# PWM-Generator.net
KiCad netlist of a schematic drawn in Altium Designer
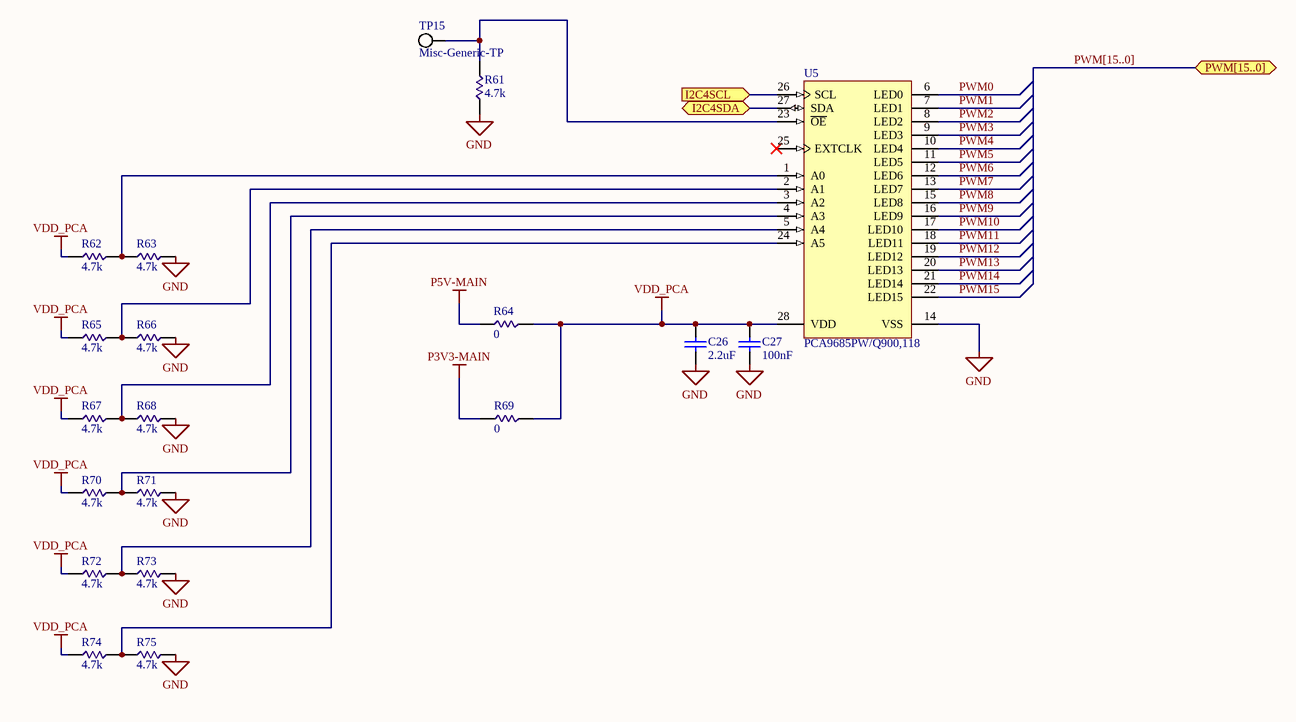
[diagram p0: PWM-Generator.SchDoc]

(export (version "E")
  (design (tool "Eeschema 10.0.6"))
  (components
    (comp (ref "C26")
      (value "2.2uF")
      (footprint "FOOTPRINT-0805-GEN")
      (description "Capacitor")
      (fields (field (name "Comment") "C0805C225K8RACTU") (field (name "PUBLISHER") "Altium Limited"))
      (libsource (lib "HR-Master-Integrated") (part "Capacitor-Generic-0805"))
    )
    (comp (ref "C27")
      (value "100nF")
      (footprint "FOOTPRINT-0805-GEN")
      (description "Capacitor")
      (fields (field (name "Comment") "C0805C104K8RACTU") (field (name "PUBLISHER") "Altium Limited"))
      (libsource (lib "HR-Master-Integrated") (part "Capacitor-Generic-0805"))
    )
    (comp (ref "R61")
      (value "4.7k")
      (footprint "FOOTPRINT-0805-GEN")
      (description "1/8 Watt Surface Mount Resistor")
      (fields (field (name "Comment") "SMC"))
      (libsource (lib "HR-Master-Integrated") (part "Resistor-Generic-0805-2012"))
    )
    (comp (ref "R62")
      (value "4.7k")
      (footprint "FOOTPRINT-0805-GEN")
      (description "1/8 Watt Surface Mount Resistor")
      (fields (field (name "Comment") "SMC"))
      (libsource (lib "HR-Master-Integrated") (part "Resistor-Generic-0805-2012"))
    )
    (comp (ref "R63")
      (value "4.7k")
      (footprint "FOOTPRINT-0805-GEN")
      (description "1/8 Watt Surface Mount Resistor")
      (fields (field (name "Comment") "SMC"))
      (libsource (lib "HR-Master-Integrated") (part "Resistor-Generic-0805-2012"))
    )
    (comp (ref "R64")
      (value "0")
      (footprint "FOOTPRINT-0805-GEN")
      (description "1/8 Watt Surface Mount Resistor")
      (fields (field (name "Comment") "SMC"))
      (libsource (lib "HR-Master-Integrated") (part "Resistor-Generic-0805-2012"))
    )
    (comp (ref "R65")
      (value "4.7k")
      (footprint "FOOTPRINT-0805-GEN")
      (description "1/8 Watt Surface Mount Resistor")
      (fields (field (name "Comment") "SMC"))
      (libsource (lib "HR-Master-Integrated") (part "Resistor-Generic-0805-2012"))
    )
    (comp (ref "R66")
      (value "4.7k")
      (footprint "FOOTPRINT-0805-GEN")
      (description "1/8 Watt Surface Mount Resistor")
      (fields (field (name "Comment") "SMC"))
      (libsource (lib "HR-Master-Integrated") (part "Resistor-Generic-0805-2012"))
    )
    (comp (ref "R67")
      (value "4.7k")
      (footprint "FOOTPRINT-0805-GEN")
      (description "1/8 Watt Surface Mount Resistor")
      (fields (field (name "Comment") "SMC"))
      (libsource (lib "HR-Master-Integrated") (part "Resistor-Generic-0805-2012"))
    )
    (comp (ref "R68")
      (value "4.7k")
      (footprint "FOOTPRINT-0805-GEN")
      (description "1/8 Watt Surface Mount Resistor")
      (fields (field (name "Comment") "SMC"))
      (libsource (lib "HR-Master-Integrated") (part "Resistor-Generic-0805-2012"))
    )
    (comp (ref "R69")
      (value "0")
      (footprint "FOOTPRINT-0805-GEN")
      (description "1/8 Watt Surface Mount Resistor")
      (fields (field (name "Comment") "SMC"))
      (libsource (lib "HR-Master-Integrated") (part "Resistor-Generic-0805-2012"))
    )
    (comp (ref "R70")
      (value "4.7k")
      (footprint "FOOTPRINT-0805-GEN")
      (description "1/8 Watt Surface Mount Resistor")
      (fields (field (name "Comment") "SMC"))
      (libsource (lib "HR-Master-Integrated") (part "Resistor-Generic-0805-2012"))
    )
    (comp (ref "R71")
      (value "4.7k")
      (footprint "FOOTPRINT-0805-GEN")
      (description "1/8 Watt Surface Mount Resistor")
      (fields (field (name "Comment") "SMC"))
      (libsource (lib "HR-Master-Integrated") (part "Resistor-Generic-0805-2012"))
    )
    (comp (ref "R72")
      (value "4.7k")
      (footprint "FOOTPRINT-0805-GEN")
      (description "1/8 Watt Surface Mount Resistor")
      (fields (field (name "Comment") "SMC"))
      (libsource (lib "HR-Master-Integrated") (part "Resistor-Generic-0805-2012"))
    )
    (comp (ref "R73")
      (value "4.7k")
      (footprint "FOOTPRINT-0805-GEN")
      (description "1/8 Watt Surface Mount Resistor")
      (fields (field (name "Comment") "SMC"))
      (libsource (lib "HR-Master-Integrated") (part "Resistor-Generic-0805-2012"))
    )
    (comp (ref "R74")
      (value "4.7k")
      (footprint "FOOTPRINT-0805-GEN")
      (description "1/8 Watt Surface Mount Resistor")
      (fields (field (name "Comment") "SMC"))
      (libsource (lib "HR-Master-Integrated") (part "Resistor-Generic-0805-2012"))
    )
    (comp (ref "R75")
      (value "4.7k")
      (footprint "FOOTPRINT-0805-GEN")
      (description "1/8 Watt Surface Mount Resistor")
      (fields (field (name "Comment") "SMC"))
      (libsource (lib "HR-Master-Integrated") (part "Resistor-Generic-0805-2012"))
    )
    (comp (ref "TP15")
      (value "Misc-Generic-TP")
      (footprint "FOOTPRINT-GENERIC-TP-VIA-1MM")
      (libsource (lib "Generic") (part "Misc-Generic-TP"))
    )
    (comp (ref "U5")
      (value "PCA9685PW/Q900,118")
      (footprint "FOOTPRINT-NXP-PCA9685")
      (fields (field (name "PARTNUMBER") "PCA9685"))
      (libsource (lib "HR-Master-Integrated") (part "IC-NXP-PCA9685"))
    )
  )
  (nets
    (net (code "1") (name "/I2C4SCL") (class "Default")
      (node (ref "U5") (pin "26") (pinfunction "SCL_26") (pintype "input"))
    )
    (net (code "2") (name "/I2C4SDA") (class "Default")
      (node (ref "U5") (pin "27") (pinfunction "SDA_27") (pintype "bidirectional"))
    )
    (net (code "3") (name "/PWM0") (class "Default")
      (node (ref "U5") (pin "6") (pinfunction "LED0_6") (pintype "tri_state"))
    )
    (net (code "4") (name "/PWM1") (class "Default")
      (node (ref "U5") (pin "7") (pinfunction "LED1_7") (pintype "tri_state"))
    )
    (net (code "5") (name "/PWM2") (class "Default")
      (node (ref "U5") (pin "8") (pinfunction "LED2_8") (pintype "tri_state"))
    )
    (net (code "6") (name "/PWM3") (class "Default")
      (node (ref "U5") (pin "9") (pinfunction "LED3_9") (pintype "tri_state"))
    )
    (net (code "7") (name "/PWM4") (class "Default")
      (node (ref "U5") (pin "10") (pinfunction "LED4_10") (pintype "tri_state"))
    )
    (net (code "8") (name "/PWM5") (class "Default")
      (node (ref "U5") (pin "11") (pinfunction "LED5_11") (pintype "tri_state"))
    )
    (net (code "9") (name "/PWM6") (class "Default")
      (node (ref "U5") (pin "12") (pinfunction "LED6_12") (pintype "tri_state"))
    )
    (net (code "10") (name "/PWM7") (class "Default")
      (node (ref "U5") (pin "13") (pinfunction "LED7_13") (pintype "tri_state"))
    )
    (net (code "11") (name "/PWM8") (class "Default")
      (node (ref "U5") (pin "15") (pinfunction "LED8_15") (pintype "tri_state"))
    )
    (net (code "12") (name "/PWM9") (class "Default")
      (node (ref "U5") (pin "16") (pinfunction "LED9_16") (pintype "tri_state"))
    )
    (net (code "13") (name "/PWM10") (class "Default")
      (node (ref "U5") (pin "17") (pinfunction "LED10_17") (pintype "tri_state"))
    )
    (net (code "14") (name "/PWM11") (class "Default")
      (node (ref "U5") (pin "18") (pinfunction "LED11_18") (pintype "tri_state"))
    )
    (net (code "15") (name "/PWM12") (class "Default")
      (node (ref "U5") (pin "19") (pinfunction "LED12_19") (pintype "tri_state"))
    )
    (net (code "16") (name "/PWM13") (class "Default")
      (node (ref "U5") (pin "20") (pinfunction "LED13_20") (pintype "tri_state"))
    )
    (net (code "17") (name "/PWM14") (class "Default")
      (node (ref "U5") (pin "21") (pinfunction "LED14_21") (pintype "tri_state"))
    )
    (net (code "18") (name "/PWM15") (class "Default")
      (node (ref "U5") (pin "22") (pinfunction "LED15_22") (pintype "tri_state"))
    )
    (net (code "20") (name "GND") (class "Default")
      (node (ref "C26") (pin "2") (pinfunction "2_2") (pintype "passive"))
      (node (ref "C27") (pin "1") (pinfunction "1_1") (pintype "passive"))
      (node (ref "R61") (pin "1") (pinfunction "1_1") (pintype "passive"))
      (node (ref "R63") (pin "2") (pinfunction "2_2") (pintype "passive"))
      (node (ref "R66") (pin "2") (pinfunction "2_2") (pintype "passive"))
      (node (ref "R68") (pin "2") (pinfunction "2_2") (pintype "passive"))
      (node (ref "R71") (pin "2") (pinfunction "2_2") (pintype "passive"))
      (node (ref "R73") (pin "2") (pinfunction "2_2") (pintype "passive"))
      (node (ref "R75") (pin "2") (pinfunction "2_2") (pintype "passive"))
      (node (ref "U5") (pin "14") (pinfunction "VSS_14") (pintype "power_in"))
    )
    (net (code "21") (name "Net-(TP15-TP)") (class "Default")
      (node (ref "R61") (pin "2") (pinfunction "2_2") (pintype "passive"))
      (node (ref "TP15") (pin "1") (pinfunction "TP_1") (pintype "passive"))
      (node (ref "U5") (pin "23") (pinfunction "~{OE}_23") (pintype "input"))
    )
    (net (code "22") (name "Net-(U5-A0)") (class "Default")
      (node (ref "R62") (pin "1") (pinfunction "1_1") (pintype "passive"))
      (node (ref "R63") (pin "1") (pinfunction "1_1") (pintype "passive"))
      (node (ref "U5") (pin "1") (pinfunction "A0_1") (pintype "input"))
    )
    (net (code "23") (name "Net-(U5-A1)") (class "Default")
      (node (ref "R65") (pin "1") (pinfunction "1_1") (pintype "passive"))
      (node (ref "R66") (pin "1") (pinfunction "1_1") (pintype "passive"))
      (node (ref "U5") (pin "2") (pinfunction "A1_2") (pintype "input"))
    )
    (net (code "24") (name "Net-(U5-A2)") (class "Default")
      (node (ref "R67") (pin "1") (pinfunction "1_1") (pintype "passive"))
      (node (ref "R68") (pin "1") (pinfunction "1_1") (pintype "passive"))
      (node (ref "U5") (pin "3") (pinfunction "A2_3") (pintype "input"))
    )
    (net (code "25") (name "Net-(U5-A3)") (class "Default")
      (node (ref "R70") (pin "1") (pinfunction "1_1") (pintype "passive"))
      (node (ref "R71") (pin "1") (pinfunction "1_1") (pintype "passive"))
      (node (ref "U5") (pin "4") (pinfunction "A3_4") (pintype "input"))
    )
    (net (code "26") (name "Net-(U5-A4)") (class "Default")
      (node (ref "R72") (pin "1") (pinfunction "1_1") (pintype "passive"))
      (node (ref "R73") (pin "1") (pinfunction "1_1") (pintype "passive"))
      (node (ref "U5") (pin "5") (pinfunction "A4_5") (pintype "input"))
    )
    (net (code "27") (name "Net-(U5-A5)") (class "Default")
      (node (ref "R74") (pin "1") (pinfunction "1_1") (pintype "passive"))
      (node (ref "R75") (pin "1") (pinfunction "1_1") (pintype "passive"))
      (node (ref "U5") (pin "24") (pinfunction "A5_24") (pintype "input"))
    )
    (net (code "28") (name "P3V3-MAIN") (class "Default")
      (node (ref "R69") (pin "1") (pinfunction "1_1") (pintype "passive"))
    )
    (net (code "29") (name "P5V-MAIN") (class "Default")
      (node (ref "R64") (pin "2") (pinfunction "2_2") (pintype "passive"))
    )
    (net (code "30") (name "VDD_PCA") (class "Default")
      (node (ref "C26") (pin "1") (pinfunction "1_1") (pintype "passive"))
      (node (ref "C27") (pin "2") (pinfunction "2_2") (pintype "passive"))
      (node (ref "R62") (pin "2") (pinfunction "2_2") (pintype "passive"))
      (node (ref "R64") (pin "1") (pinfunction "1_1") (pintype "passive"))
      (node (ref "R65") (pin "2") (pinfunction "2_2") (pintype "passive"))
      (node (ref "R67") (pin "2") (pinfunction "2_2") (pintype "passive"))
      (node (ref "R69") (pin "2") (pinfunction "2_2") (pintype "passive"))
      (node (ref "R70") (pin "2") (pinfunction "2_2") (pintype "passive"))
      (node (ref "R72") (pin "2") (pinfunction "2_2") (pintype "passive"))
      (node (ref "R74") (pin "2") (pinfunction "2_2") (pintype "passive"))
      (node (ref "U5") (pin "28") (pinfunction "VDD_28") (pintype "power_in"))
    )
    (net (code "31") (name "unconnected-(U5-EXTCLK-Pad25)") (class "Default")
      (node (ref "U5") (pin "25") (pinfunction "EXTCLK_25") (pintype "input+no_connect"))
    )
  )
)
